# CPU.net
KiCad netlist of a schematic drawn in Altium Designer
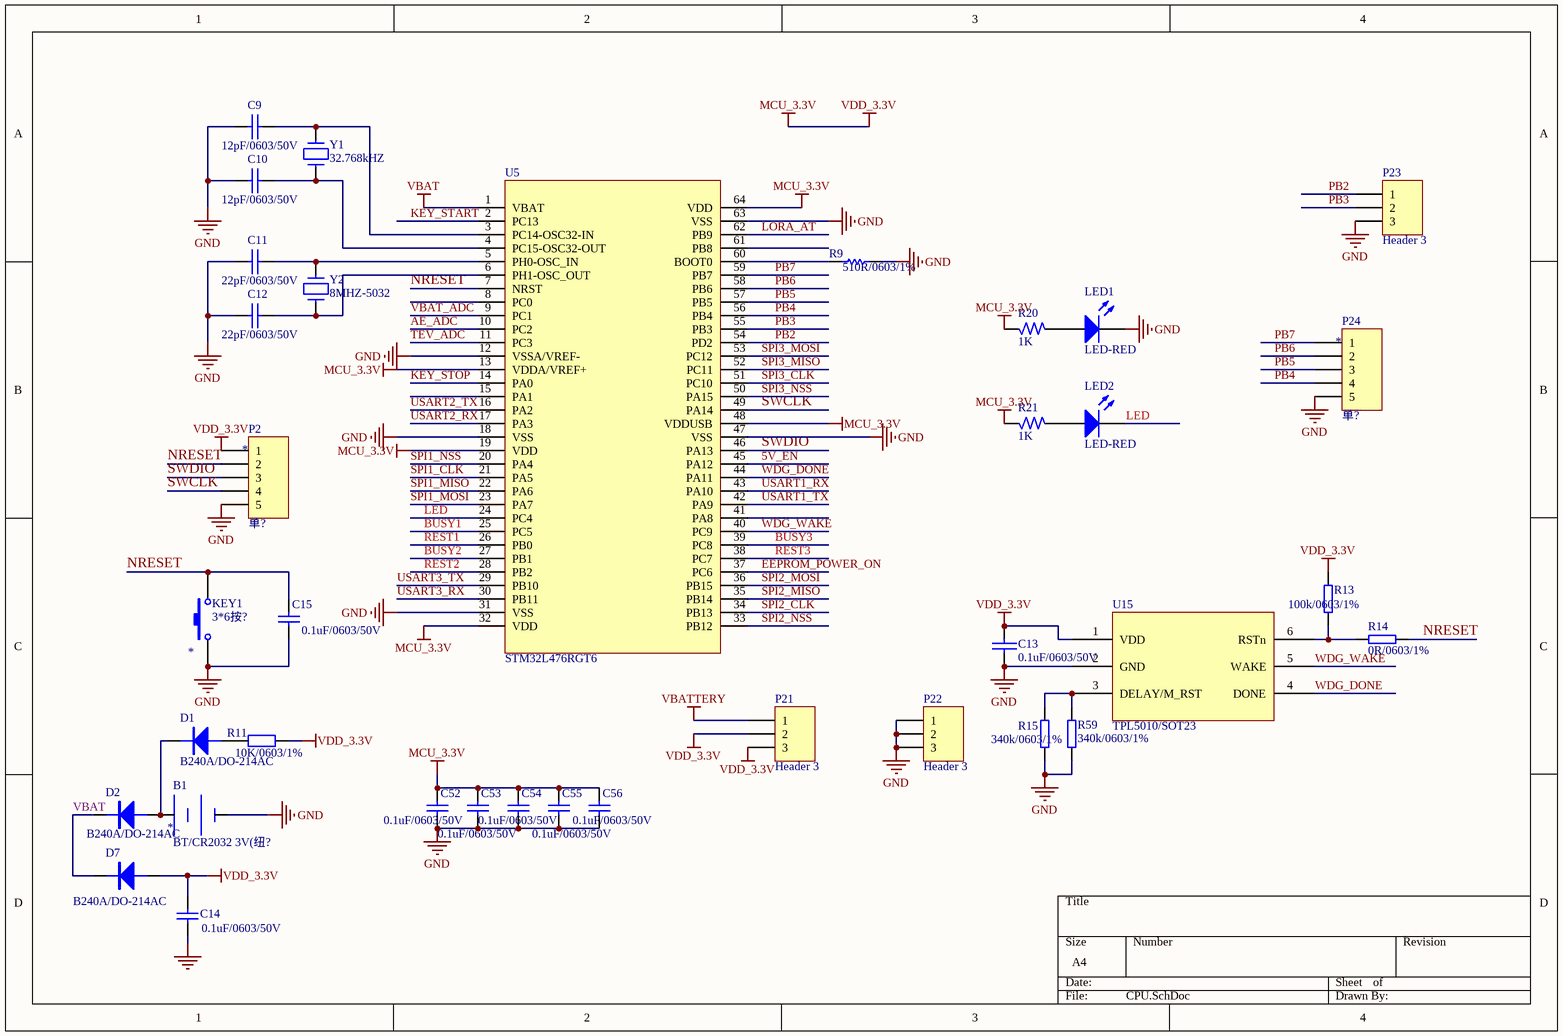
[diagram p0: CPU.SchDoc]

(export (version "E")
  (design (tool "Eeschema 10.0.6"))
  (components
    (comp (ref "B1")
      (value "*")
      (footprint "LI1220_1")
      (fields (field (name "ALTIUM_UNNAMED_1") "BT/CR2032 3V(纽?"))
      (libsource (lib "*") (part "VBAT"))
    )
    (comp (ref "C9")
      (value "12pF/0603/50V")
      (footprint "0603")
      (description "Capacitor")
      (libsource (lib "*") (part "CAP"))
    )
    (comp (ref "C10")
      (value "12pF/0603/50V")
      (footprint "0603")
      (description "Capacitor")
      (libsource (lib "*") (part "CAP"))
    )
    (comp (ref "C11")
      (value "22pF/0603/50V")
      (footprint "0603")
      (description "Capacitor")
      (libsource (lib "*") (part "CAP"))
    )
    (comp (ref "C12")
      (value "22pF/0603/50V")
      (footprint "0603")
      (description "Capacitor")
      (libsource (lib "*") (part "CAP"))
    )
    (comp (ref "C13")
      (value "0.1uF/0603/50V")
      (footprint "0603")
      (description "Capacitor")
      (libsource (lib "") (part "CAP_1"))
    )
    (comp (ref "C14")
      (value "0.1uF/0603/50V")
      (footprint "0603")
      (description "Capacitor")
      (fields (field (name "PUBLISHER") "Altium Limited"))
      (libsource (lib "Miscellaneous Devices") (part "Cap"))
    )
    (comp (ref "C15")
      (value "0.1uF/0603/50V")
      (footprint "0603")
      (description "Capacitor")
      (fields (field (name "PUBLISHER") "Altium Limited"))
      (libsource (lib "*") (part "Cap"))
    )
    (comp (ref "C52")
      (value "0.1uF/0603/50V")
      (footprint "0603")
      (description "Capacitor")
      (fields (field (name "PUBLISHER") "Altium Limited"))
      (libsource (lib "*") (part "Cap"))
    )
    (comp (ref "C53")
      (value "0.1uF/0603/50V")
      (footprint "0603")
      (description "Capacitor")
      (fields (field (name "PUBLISHER") "Altium Limited"))
      (libsource (lib "*") (part "Cap"))
    )
    (comp (ref "C54")
      (value "0.1uF/0603/50V")
      (footprint "0603")
      (description "Capacitor")
      (fields (field (name "PUBLISHER") "Altium Limited"))
      (libsource (lib "*") (part "Cap"))
    )
    (comp (ref "C55")
      (value "0.1uF/0603/50V")
      (footprint "0603")
      (description "Capacitor")
      (fields (field (name "PUBLISHER") "Altium Limited"))
      (libsource (lib "*") (part "Cap"))
    )
    (comp (ref "C56")
      (value "0.1uF/0603/50V")
      (footprint "0603")
      (description "Capacitor")
      (fields (field (name "PUBLISHER") "Altium Limited"))
      (libsource (lib "*") (part "Cap"))
    )
    (comp (ref "D1")
      (value "B240A/DO-214AC")
      (footprint "DO-214AC")
      (description "Diode")
      (libsource (lib "*") (part "DIODE"))
    )
    (comp (ref "D2")
      (value "B240A/DO-214AC")
      (footprint "DO-214AC")
      (description "Diode")
      (libsource (lib "*") (part "DIODE"))
    )
    (comp (ref "D7")
      (value "B240A/DO-214AC")
      (footprint "DO-214AC")
      (description "Diode")
      (libsource (lib "*") (part "DIODE"))
    )
    (comp (ref "KEY1")
      (value "*")
      (footprint "KEY-3X6mm")
      (description "Switch")
      (fields (field (name "ALTIUM_UNNAMED_1") "3*6按?") (field (name "PUBLISHER") "Altium Limited"))
      (libsource (lib "*") (part "SW-PB"))
    )
    (comp (ref "LED1")
      (value "LED-RED")
      (footprint "LED-0603")
      (description "LED-RED,5V,30mA,90mW,1.6*0.8mm")
      (libsource (lib "LTD") (part "LED-RED-0603"))
    )
    (comp (ref "LED2")
      (value "LED-RED")
      (footprint "LED-0603")
      (description "LED-RED,5V,30mA,90mW,1.6*0.8mm")
      (libsource (lib "LTD") (part "LED-RED-0603"))
    )
    (comp (ref "P2")
      (value "*")
      (footprint "HDR1X5")
      (description "Header, 5-Pin")
      (fields (field (name "ALTIUM_UNNAMED_1") "单?") (field (name "PUBLISHER") "Altium Limited"))
      (libsource (lib "Miscellaneous Connectors") (part "Header 5"))
    )
    (comp (ref "P21")
      (value "Header 3")
      (footprint "HDR1X3")
      (description "Header, 3-Pin")
      (fields (field (name "PUBLISHER") "Altium Limited"))
      (libsource (lib "Miscellaneous Connectors") (part "Header 3"))
    )
    (comp (ref "P22")
      (value "Header 3")
      (footprint "HDR1X3")
      (description "Header, 3-Pin")
      (fields (field (name "PUBLISHER") "Altium Limited"))
      (libsource (lib "Miscellaneous Connectors") (part "Header 3"))
    )
    (comp (ref "P23")
      (value "Header 3")
      (footprint "HDR1X3")
      (description "Header, 3-Pin")
      (fields (field (name "PUBLISHER") "Altium Limited"))
      (libsource (lib "Miscellaneous Connectors") (part "Header 3"))
    )
    (comp (ref "P24")
      (value "*")
      (footprint "HDR1X5")
      (description "Header, 5-Pin")
      (fields (field (name "ALTIUM_UNNAMED_1") "单?") (field (name "PUBLISHER") "Altium Limited"))
      (libsource (lib "Miscellaneous Connectors") (part "Header 5"))
    )
    (comp (ref "R9")
      (value "510R/0603/1%")
      (footprint "0603")
      (description "Resistor")
      (libsource (lib "5D_DEVICE") (part "RES"))
    )
    (comp (ref "R11")
      (value "10K/0603/1%")
      (footprint "0603")
      (description "Semiconductor Resistor")
      (fields (field (name "PUBLISHER") "Altium Limited"))
      (libsource (lib "Miscellaneous Devices") (part "Res Semi"))
    )
    (comp (ref "R13") (value "100k/0603/1%") (footprint "0603") (libsource (lib "*") (part "RES")))
    (comp (ref "R14") (value "0R/0603/1%") (footprint "0603") (libsource (lib "*") (part "RES")))
    (comp (ref "R15") (value "340k/0603/1%") (footprint "0603") (libsource (lib "*") (part "RES")))
    (comp (ref "R20")
      (value "1K")
      (footprint "R-0603")
      (description "RES,1K,1/10W,1%,0603")
      (libsource (lib "PD100") (part "RES-1K-1%-0603"))
    )
    (comp (ref "R21")
      (value "1K")
      (footprint "R-0603")
      (description "RES,1K,1/10W,1%,0603")
      (libsource (lib "PD100") (part "RES-1K-1%-0603"))
    )
    (comp (ref "R59") (value "340k/0603/1%") (footprint "0603") (libsource (lib "*") (part "RES")))
    (comp (ref "U5")
      (value "STM32L476RGT6")
      (footprint "LQFP-64-10X10-0.5")
      (libsource (lib "GTT300") (part "STM32L476R"))
    )
    (comp (ref "U15") (value "TPL5010/SOT23") (footprint "SOT23-6") (libsource (lib "局放") (part "TPL5010")))
    (comp (ref "Y1")
      (value "32.768kHZ")
      (footprint "32.768K")
      (description "Crystal")
      (libsource (lib "*") (part "CRYSTAL"))
    )
    (comp (ref "Y2")
      (value "8MHZ-5032")
      (footprint "XAL")
      (description "Crystal")
      (libsource (lib "*") (part "CRYSTAL"))
    )
  )
  (nets
    (net (code "1") (name "/5V_EN") (class "Default")
      (node (ref "U5") (pin "45") (pinfunction "PA12_45") (pintype "passive"))
    )
    (net (code "2") (name "/AE_ADC") (class "Default")
      (node (ref "U5") (pin "10") (pinfunction "PC2_10") (pintype "passive"))
    )
    (net (code "3") (name "/BUSY1") (class "Default")
      (node (ref "U5") (pin "25") (pinfunction "PC5_25") (pintype "passive"))
    )
    (net (code "4") (name "/BUSY2") (class "Default")
      (node (ref "U5") (pin "27") (pinfunction "PB1_27") (pintype "passive"))
    )
    (net (code "5") (name "/BUSY3") (class "Default")
      (node (ref "U5") (pin "39") (pinfunction "PC8_39") (pintype "passive"))
    )
    (net (code "6") (name "/EEPROM_POWER_ON") (class "Default")
      (node (ref "U5") (pin "37") (pinfunction "PC6_37") (pintype "passive"))
    )
    (net (code "7") (name "/KEY_START") (class "Default")
      (node (ref "U5") (pin "2") (pinfunction "PC13_2") (pintype "passive"))
    )
    (net (code "8") (name "/KEY_STOP") (class "Default")
      (node (ref "U5") (pin "14") (pinfunction "PA0_14") (pintype "passive"))
    )
    (net (code "9") (name "/LED") (class "Default")
      (node (ref "LED2") (pin "2") (pinfunction "K_2") (pintype "passive"))
      (node (ref "U5") (pin "24") (pinfunction "PC4_24") (pintype "passive"))
    )
    (net (code "10") (name "/LORA_AT") (class "Default")
      (node (ref "U5") (pin "62") (pinfunction "PB9_62") (pintype "passive"))
    )
    (net (code "11") (name "/NRESET") (class "Default")
      (node (ref "C15") (pin "2") (pinfunction "2_2") (pintype "passive"))
      (node (ref "KEY1") (pin "2") (pinfunction "2_2") (pintype "passive"))
      (node (ref "P2") (pin "2") (pinfunction "2_2") (pintype "passive"))
      (node (ref "R14") (pin "1") (pinfunction "1_1") (pintype "passive"))
      (node (ref "U5") (pin "7") (pinfunction "NRST_7") (pintype "passive"))
    )
    (net (code "12") (name "/PB2") (class "Default")
      (node (ref "P23") (pin "1") (pinfunction "1_1") (pintype "passive"))
      (node (ref "U5") (pin "54") (pinfunction "PD2_54") (pintype "passive"))
    )
    (net (code "13") (name "/PB3") (class "Default")
      (node (ref "P23") (pin "2") (pinfunction "2_2") (pintype "passive"))
      (node (ref "U5") (pin "55") (pinfunction "PB3_55") (pintype "passive"))
    )
    (net (code "14") (name "/PB4") (class "Default")
      (node (ref "P24") (pin "4") (pinfunction "4_4") (pintype "passive"))
      (node (ref "U5") (pin "56") (pinfunction "PB4_56") (pintype "passive"))
    )
    (net (code "15") (name "/PB5") (class "Default")
      (node (ref "P24") (pin "3") (pinfunction "3_3") (pintype "passive"))
      (node (ref "U5") (pin "57") (pinfunction "PB5_57") (pintype "passive"))
    )
    (net (code "16") (name "/PB6") (class "Default")
      (node (ref "P24") (pin "2") (pinfunction "2_2") (pintype "passive"))
      (node (ref "U5") (pin "58") (pinfunction "PB6_58") (pintype "passive"))
    )
    (net (code "17") (name "/PB7") (class "Default")
      (node (ref "P24") (pin "1") (pinfunction "1_1") (pintype "passive"))
      (node (ref "U5") (pin "59") (pinfunction "PB7_59") (pintype "passive"))
    )
    (net (code "18") (name "/REST1") (class "Default")
      (node (ref "U5") (pin "26") (pinfunction "PB0_26") (pintype "passive"))
    )
    (net (code "19") (name "/REST2") (class "Default")
      (node (ref "U5") (pin "28") (pinfunction "PB2_28") (pintype "passive"))
    )
    (net (code "20") (name "/REST3") (class "Default")
      (node (ref "U5") (pin "38") (pinfunction "PC7_38") (pintype "passive"))
    )
    (net (code "21") (name "/SPI1_CLK") (class "Default")
      (node (ref "U5") (pin "21") (pinfunction "PA5_21") (pintype "passive"))
    )
    (net (code "22") (name "/SPI1_MISO") (class "Default")
      (node (ref "U5") (pin "22") (pinfunction "PA6_22") (pintype "passive"))
    )
    (net (code "23") (name "/SPI1_MOSI") (class "Default")
      (node (ref "U5") (pin "23") (pinfunction "PA7_23") (pintype "passive"))
    )
    (net (code "24") (name "/SPI1_NSS") (class "Default")
      (node (ref "U5") (pin "20") (pinfunction "PA4_20") (pintype "passive"))
    )
    (net (code "25") (name "/SPI2_CLK") (class "Default")
      (node (ref "U5") (pin "34") (pinfunction "PB13_34") (pintype "passive"))
    )
    (net (code "26") (name "/SPI2_MISO") (class "Default")
      (node (ref "U5") (pin "35") (pinfunction "PB14_35") (pintype "passive"))
    )
    (net (code "27") (name "/SPI2_MOSI") (class "Default")
      (node (ref "U5") (pin "36") (pinfunction "PB15_36") (pintype "passive"))
    )
    (net (code "28") (name "/SPI2_NSS") (class "Default")
      (node (ref "U5") (pin "33") (pinfunction "PB12_33") (pintype "passive"))
    )
    (net (code "29") (name "/SPI3_CLK") (class "Default")
      (node (ref "U5") (pin "51") (pinfunction "PC10_51") (pintype "passive"))
    )
    (net (code "30") (name "/SPI3_MISO") (class "Default")
      (node (ref "U5") (pin "52") (pinfunction "PC11_52") (pintype "passive"))
    )
    (net (code "31") (name "/SPI3_MOSI") (class "Default")
      (node (ref "U5") (pin "53") (pinfunction "PC12_53") (pintype "passive"))
    )
    (net (code "32") (name "/SPI3_NSS") (class "Default")
      (node (ref "U5") (pin "50") (pinfunction "PA15_50") (pintype "passive"))
    )
    (net (code "33") (name "/SWCLK") (class "Default")
      (node (ref "P2") (pin "4") (pinfunction "4_4") (pintype "passive"))
      (node (ref "U5") (pin "49") (pinfunction "PA14_49") (pintype "passive"))
    )
    (net (code "34") (name "/SWDIO") (class "Default")
      (node (ref "P2") (pin "3") (pinfunction "3_3") (pintype "passive"))
      (node (ref "U5") (pin "46") (pinfunction "PA13_46") (pintype "passive"))
    )
    (net (code "35") (name "/TEV_ADC") (class "Default")
      (node (ref "U5") (pin "11") (pinfunction "PC3_11") (pintype "passive"))
    )
    (net (code "36") (name "/USART1_RX") (class "Default")
      (node (ref "U5") (pin "43") (pinfunction "PA10_43") (pintype "passive"))
    )
    (net (code "37") (name "/USART1_TX") (class "Default")
      (node (ref "U5") (pin "42") (pinfunction "PA9_42") (pintype "passive"))
    )
    (net (code "38") (name "/USART2_RX") (class "Default")
      (node (ref "U5") (pin "17") (pinfunction "PA3_17") (pintype "passive"))
    )
    (net (code "39") (name "/USART2_TX") (class "Default")
      (node (ref "U5") (pin "16") (pinfunction "PA2_16") (pintype "passive"))
    )
    (net (code "40") (name "/USART3_RX") (class "Default")
      (node (ref "U5") (pin "30") (pinfunction "PB11_30") (pintype "passive"))
    )
    (net (code "41") (name "/USART3_TX") (class "Default")
      (node (ref "U5") (pin "29") (pinfunction "PB10_29") (pintype "passive"))
    )
    (net (code "42") (name "/VBAT_ADC") (class "Default")
      (node (ref "U5") (pin "9") (pinfunction "PC1_9") (pintype "passive"))
    )
    (net (code "43") (name "/WDG_DONE") (class "Default")
      (node (ref "U15") (pin "4") (pinfunction "DONE_4") (pintype "passive"))
      (node (ref "U5") (pin "44") (pinfunction "PA11_44") (pintype "passive"))
    )
    (net (code "44") (name "/WDG_WAKE") (class "Default")
      (node (ref "U15") (pin "5") (pinfunction "WAKE_5") (pintype "passive"))
      (node (ref "U5") (pin "40") (pinfunction "PC9_40") (pintype "passive"))
    )
    (net (code "45") (name "GND") (class "Default")
      (node (ref "B1") (pin "2") (pintype "passive"))
      (node (ref "C10") (pin "1") (pinfunction "1_1") (pintype "passive"))
      (node (ref "C11") (pin "1") (pinfunction "1_1") (pintype "passive"))
      (node (ref "C12") (pin "1") (pinfunction "1_1") (pintype "passive"))
      (node (ref "C13") (pin "2") (pinfunction "2_2") (pintype "passive"))
      (node (ref "C14") (pin "1") (pinfunction "1_1") (pintype "passive"))
      (node (ref "C15") (pin "1") (pinfunction "1_1") (pintype "passive"))
      (node (ref "C52") (pin "1") (pinfunction "1_1") (pintype "passive"))
      (node (ref "C53") (pin "1") (pinfunction "1_1") (pintype "passive"))
      (node (ref "C54") (pin "1") (pinfunction "1_1") (pintype "passive"))
      (node (ref "C55") (pin "1") (pinfunction "1_1") (pintype "passive"))
      (node (ref "C56") (pin "1") (pinfunction "1_1") (pintype "passive"))
      (node (ref "C9") (pin "1") (pinfunction "1_1") (pintype "passive"))
      (node (ref "KEY1") (pin "1") (pinfunction "1_1") (pintype "passive"))
      (node (ref "LED1") (pin "2") (pinfunction "K_2") (pintype "passive"))
      (node (ref "P2") (pin "5") (pinfunction "5_5") (pintype "passive"))
      (node (ref "P22") (pin "1") (pinfunction "1_1") (pintype "passive"))
      (node (ref "P22") (pin "2") (pinfunction "2_2") (pintype "passive"))
      (node (ref "P22") (pin "3") (pinfunction "3_3") (pintype "passive"))
      (node (ref "P23") (pin "3") (pinfunction "3_3") (pintype "passive"))
      (node (ref "P24") (pin "5") (pinfunction "5_5") (pintype "passive"))
      (node (ref "R15") (pin "1") (pinfunction "1_1") (pintype "passive"))
      (node (ref "R59") (pin "1") (pinfunction "1_1") (pintype "passive"))
      (node (ref "R9") (pin "2") (pinfunction "2_2") (pintype "passive"))
      (node (ref "U15") (pin "2") (pinfunction "GND_2") (pintype "passive"))
      (node (ref "U5") (pin "12") (pinfunction "VSSA/VREF-_12") (pintype "passive"))
      (node (ref "U5") (pin "18") (pinfunction "VSS_18") (pintype "passive"))
      (node (ref "U5") (pin "31") (pinfunction "VSS_31") (pintype "passive"))
      (node (ref "U5") (pin "47") (pinfunction "VSS_47") (pintype "passive"))
      (node (ref "U5") (pin "63") (pinfunction "VSS_63") (pintype "passive"))
    )
    (net (code "46") (name "MCU_3.3V") (class "Default")
      (node (ref "C13") (pin "1") (pinfunction "1_1") (pintype "passive"))
      (node (ref "C14") (pin "2") (pinfunction "2_2") (pintype "passive"))
      (node (ref "C52") (pin "2") (pinfunction "2_2") (pintype "passive"))
      (node (ref "C53") (pin "2") (pinfunction "2_2") (pintype "passive"))
      (node (ref "C54") (pin "2") (pinfunction "2_2") (pintype "passive"))
      (node (ref "C55") (pin "2") (pinfunction "2_2") (pintype "passive"))
      (node (ref "C56") (pin "2") (pinfunction "2_2") (pintype "passive"))
      (node (ref "D7") (pin "1") (pinfunction "A_1") (pintype "passive"))
      (node (ref "P2") (pin "1") (pinfunction "1_1") (pintype "passive"))
      (node (ref "P21") (pin "2") (pinfunction "2_2") (pintype "passive"))
      (node (ref "P21") (pin "3") (pinfunction "3_3") (pintype "passive"))
      (node (ref "R11") (pin "1") (pinfunction "1_1") (pintype "passive"))
      (node (ref "R13") (pin "2") (pinfunction "2_2") (pintype "passive"))
      (node (ref "R20") (pin "1") (pintype "passive"))
      (node (ref "R21") (pin "1") (pintype "passive"))
      (node (ref "U15") (pin "1") (pinfunction "VDD_1") (pintype "passive"))
      (node (ref "U5") (pin "13") (pinfunction "VDDA/VREF+_13") (pintype "passive"))
      (node (ref "U5") (pin "19") (pinfunction "VDD_19") (pintype "passive"))
      (node (ref "U5") (pin "32") (pinfunction "VDD_32") (pintype "passive"))
      (node (ref "U5") (pin "48") (pinfunction "VDDUSB_48") (pintype "passive"))
      (node (ref "U5") (pin "64") (pinfunction "VDD_64") (pintype "passive"))
    )
    (net (code "47") (name "Net-(D1-A)") (class "Default")
      (node (ref "D1") (pin "1") (pinfunction "A_1") (pintype "passive"))
      (node (ref "R11") (pin "2") (pinfunction "2_2") (pintype "passive"))
    )
    (net (code "48") (name "Net-(D1-K)") (class "Default")
      (node (ref "B1") (pin "1") (pintype "passive"))
      (node (ref "D1") (pin "2") (pinfunction "K_2") (pintype "passive"))
      (node (ref "D2") (pin "1") (pinfunction "A_1") (pintype "passive"))
    )
    (net (code "49") (name "Net-(LED1-A)") (class "Default")
      (node (ref "LED1") (pin "1") (pinfunction "A_1") (pintype "passive"))
      (node (ref "R20") (pin "2") (pintype "passive"))
    )
    (net (code "50") (name "Net-(LED2-A)") (class "Default")
      (node (ref "LED2") (pin "1") (pinfunction "A_1") (pintype "passive"))
      (node (ref "R21") (pin "2") (pintype "passive"))
    )
    (net (code "51") (name "Net-(U5-BOOT0)") (class "Default")
      (node (ref "R9") (pin "1") (pinfunction "1_1") (pintype "passive"))
      (node (ref "U5") (pin "60") (pinfunction "BOOT0_60") (pintype "passive"))
    )
    (net (code "52") (name "Net-(U5-PC14-OSC32-IN)") (class "Default")
      (node (ref "C9") (pin "2") (pinfunction "2_2") (pintype "passive"))
      (node (ref "U5") (pin "3") (pinfunction "PC14-OSC32-IN_3") (pintype "passive"))
      (node (ref "Y1") (pin "1") (pinfunction "1_1") (pintype "passive"))
    )
    (net (code "53") (name "Net-(U5-PC15-OSC32-OUT)") (class "Default")
      (node (ref "C10") (pin "2") (pinfunction "2_2") (pintype "passive"))
      (node (ref "U5") (pin "4") (pinfunction "PC15-OSC32-OUT_4") (pintype "passive"))
      (node (ref "Y1") (pin "2") (pinfunction "2_2") (pintype "passive"))
    )
    (net (code "54") (name "Net-(U5-PH0-OSC_IN)") (class "Default")
      (node (ref "C11") (pin "2") (pinfunction "2_2") (pintype "passive"))
      (node (ref "U5") (pin "5") (pinfunction "PH0-OSC_IN_5") (pintype "passive"))
      (node (ref "Y2") (pin "2") (pinfunction "2_2") (pintype "passive"))
    )
    (net (code "55") (name "Net-(U5-PH1-OSC_OUT)") (class "Default")
      (node (ref "C12") (pin "2") (pinfunction "2_2") (pintype "passive"))
      (node (ref "U5") (pin "6") (pinfunction "PH1-OSC_OUT_6") (pintype "passive"))
      (node (ref "Y2") (pin "1") (pinfunction "1_1") (pintype "passive"))
    )
    (net (code "56") (name "Net-(U15-DELAY{slash}M_RST)") (class "Default")
      (node (ref "R15") (pin "2") (pinfunction "2_2") (pintype "passive"))
      (node (ref "R59") (pin "2") (pinfunction "2_2") (pintype "passive"))
      (node (ref "U15") (pin "3") (pinfunction "DELAY/M_RST_3") (pintype "passive"))
    )
    (net (code "57") (name "Net-(U15-RSTn)") (class "Default")
      (node (ref "R13") (pin "1") (pinfunction "1_1") (pintype "passive"))
      (node (ref "R14") (pin "2") (pinfunction "2_2") (pintype "passive"))
      (node (ref "U15") (pin "6") (pinfunction "RSTn_6") (pintype "passive"))
    )
    (net (code "58") (name "VBAT") (class "Default")
      (node (ref "D2") (pin "2") (pinfunction "K_2") (pintype "passive"))
      (node (ref "D7") (pin "2") (pinfunction "K_2") (pintype "passive"))
      (node (ref "U5") (pin "1") (pinfunction "VBAT_1") (pintype "passive"))
    )
    (net (code "59") (name "VBATTERY") (class "Default")
      (node (ref "P21") (pin "1") (pinfunction "1_1") (pintype "passive"))
    )
    (net (code "60") (name "unconnected-(U5-PA1-Pad15)") (class "Default")
      (node (ref "U5") (pin "15") (pinfunction "PA1_15") (pintype "passive"))
    )
    (net (code "61") (name "unconnected-(U5-PA8-Pad41)") (class "Default")
      (node (ref "U5") (pin "41") (pinfunction "PA8_41") (pintype "passive"))
    )
    (net (code "62") (name "unconnected-(U5-PB8-Pad61)") (class "Default")
      (node (ref "U5") (pin "61") (pinfunction "PB8_61") (pintype "passive"))
    )
    (net (code "63") (name "unconnected-(U5-PC0-Pad8)") (class "Default")
      (node (ref "U5") (pin "8") (pinfunction "PC0_8") (pintype "passive"))
    )
  )
)
